# CH32F203RCT6-R1.net
KiCad netlist of a schematic drawn in Altium Designer
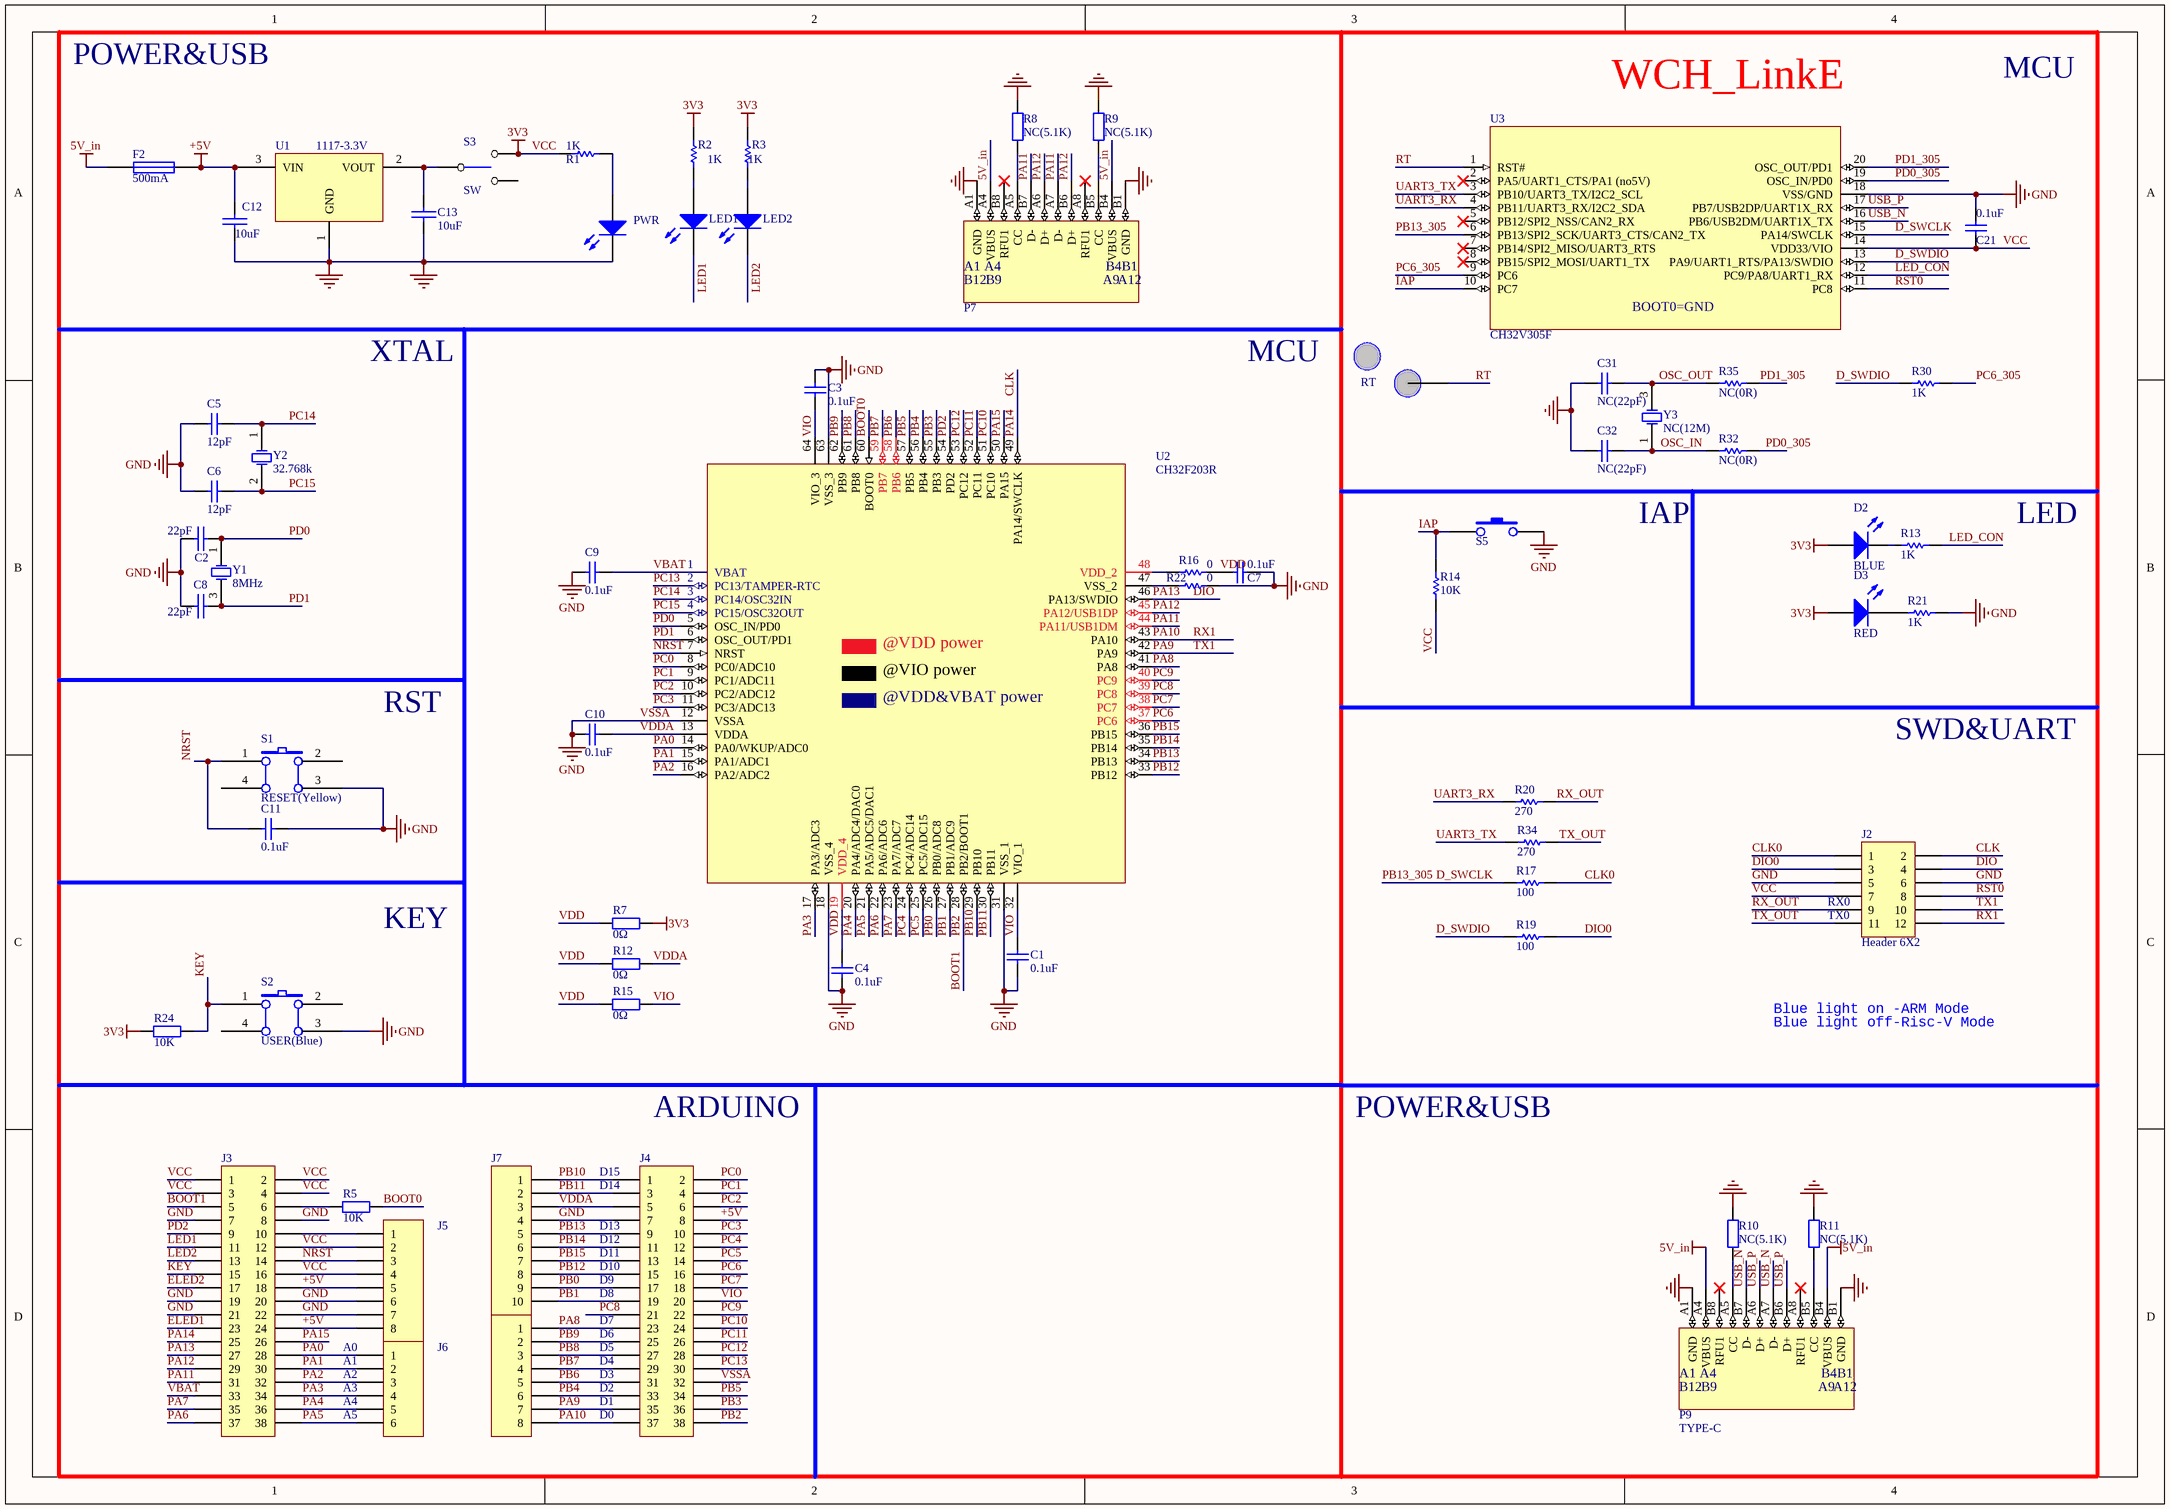
[diagram p0: CH32F203RCT6-R1.SchDoc]

(export (version "E")
  (design (tool "Eeschema 10.0.6"))
  (components
    (comp (ref "C1")
      (value "0.1uF")
      (footprint "0603_C")
      (description "Capacitor")
      (libsource (lib "Miscellaneous Devices") (part "Cap"))
    )
    (comp (ref "C2")
      (value "22pF")
      (footprint "0603_C")
      (description "Capacitor")
      (libsource (lib "*") (part "CAP"))
    )
    (comp (ref "C3")
      (value "0.1uF")
      (footprint "0603_C")
      (description "Capacitor")
      (libsource (lib "Miscellaneous Devices") (part "Cap"))
    )
    (comp (ref "C4")
      (value "0.1uF")
      (footprint "0603_C")
      (description "Capacitor")
      (libsource (lib "Miscellaneous Devices") (part "Cap"))
    )
    (comp (ref "C5")
      (value "12pF")
      (footprint "0603_C")
      (description "Capacitor")
      (libsource (lib "Miscellaneous Devices") (part "Cap"))
    )
    (comp (ref "C6")
      (value "12pF")
      (footprint "0603_C")
      (description "Capacitor")
      (libsource (lib "Miscellaneous Devices") (part "Cap"))
    )
    (comp (ref "C7")
      (value "0.1uF")
      (footprint "0603_C")
      (description "Capacitor")
      (libsource (lib "Miscellaneous Devices") (part "Cap"))
    )
    (comp (ref "C8")
      (value "22pF")
      (footprint "0603_C")
      (description "Capacitor")
      (libsource (lib "*") (part "CAP"))
    )
    (comp (ref "C9")
      (value "0.1uF")
      (footprint "0603_C")
      (description "Capacitor")
      (libsource (lib "Miscellaneous Devices") (part "Cap"))
    )
    (comp (ref "C10")
      (value "0.1uF")
      (footprint "0603_C")
      (description "Capacitor")
      (libsource (lib "Miscellaneous Devices") (part "Cap"))
    )
    (comp (ref "C11")
      (value "0.1uF")
      (footprint "0603_C")
      (description "Capacitor")
      (libsource (lib "Miscellaneous Devices") (part "Cap"))
    )
    (comp (ref "C12")
      (value "10uF")
      (footprint "3216_C")
      (description "Capacitor")
      (libsource (lib "*") (part "CAP"))
    )
    (comp (ref "C13")
      (value "10uF")
      (footprint "3216_C")
      (description "Capacitor")
      (libsource (lib "*") (part "CAP"))
    )
    (comp (ref "C21")
      (value "0.1uF")
      (footprint "0603_C")
      (description "Capacitor")
      (libsource (lib "Miscellaneous Devices") (part "Cap"))
    )
    (comp (ref "C31")
      (value "NC(22pF)")
      (footprint "0603_C")
      (description "Capacitor")
      (fields (field (name "PUBLISHER") "Altium Limited"))
      (libsource (lib "*") (part "Cap"))
    )
    (comp (ref "C32")
      (value "NC(22pF)")
      (footprint "0603_C")
      (description "Capacitor")
      (fields (field (name "PUBLISHER") "Altium Limited"))
      (libsource (lib "*") (part "Cap"))
    )
    (comp (ref "D2")
      (value "BLUE")
      (footprint "0603+")
      (description "Typical RED, GREEN, YELLOW, AMBER GaAs LED")
      (fields (field (name "PUBLISHER") "Altium Limited"))
      (libsource (lib "MYLIB") (part "D0603"))
    )
    (comp (ref "D3")
      (value "RED")
      (footprint "0603+")
      (description "Typical RED, GREEN, YELLOW, AMBER GaAs LED")
      (fields (field (name "PUBLISHER") "Altium Limited"))
      (libsource (lib "MYLIB") (part "D0603"))
    )
    (comp (ref "F2")
      (value "500mA")
      (footprint "0805")
      (description "Fuse")
      (libsource (lib "*") (part "FUSE1"))
    )
    (comp (ref "J2")
      (value "Header 6X2")
      (footprint "IDC12-2.54mm")
      (description "Header, 6-Pin, Dual row")
      (fields (field (name "PUBLISHER") "Altium Limited"))
      (libsource (lib "Miscellaneous Connectors") (part "Header 6X2"))
    )
    (comp (ref "J3")
      (value "Header 19X2")
      (footprint "IDC38-2.54mm")
      (description "Header, 19-Pin, Dual row")
      (fields (field (name "PUBLISHER") "Altium Limited"))
      (libsource (lib "Miscellaneous Connectors") (part "Header 19X2"))
    )
    (comp (ref "J4")
      (value "Header 19X2")
      (footprint "IDC38-2.54mm")
      (description "Header, 19-Pin, Dual row")
      (fields (field (name "PUBLISHER") "Altium Limited"))
      (libsource (lib "Miscellaneous Connectors") (part "Header 19X2"))
    )
    (comp (ref "J5")
      (value "Header 8")
      (footprint "SIP8-2.54mm")
      (description "Header, 8-Pin")
      (fields (field (name "PUBLISHER") "Altium Limited"))
      (libsource (lib "") (part "Header 8_1"))
    )
    (comp (ref "J6")
      (value "Header 6")
      (footprint "SIP6-2.54MM")
      (description "Header, 6-Pin")
      (fields (field (name "PUBLISHER") "Altium Limited"))
      (libsource (lib "Miscellaneous Connectors") (part "Header 6"))
    )
    (comp (ref "J7")
      (value "Header 10")
      (footprint "SIP10-2.54mm")
      (description "Header, 10-Pin")
      (fields (field (name "PUBLISHER") "Altium Limited"))
      (libsource (lib "Miscellaneous Connectors") (part "Header 10"))
    )
    (comp (ref "J8")
      (value "Header 8")
      (footprint "SIP8-2.54mm")
      (description "Header, 8-Pin")
      (fields (field (name "PUBLISHER") "Altium Limited"))
      (libsource (lib "Miscellaneous Connectors") (part "Header 8"))
    )
    (comp (ref "LED1")
      (value "LED1   blue")
      (footprint "0603+")
      (description "Typical INFRARED GaAs LED")
      (fields (field (name "PUBLISHER") "Altium Limited"))
      (libsource (lib "Miscellaneous Devices") (part "LED0"))
    )
    (comp (ref "LED2")
      (value "LED2  blue")
      (footprint "0603+")
      (description "Typical INFRARED GaAs LED")
      (fields (field (name "PUBLISHER") "Altium Limited"))
      (libsource (lib "Miscellaneous Devices") (part "LED0"))
    )
    (comp (ref "P7")
      (value "TYPE-C")
      (footprint "TYPE-C-Receptacle-2.0")
      (libsource (lib "*") (part "TYPE-C1"))
    )
    (comp (ref "P9")
      (value "TYPE-C")
      (footprint "TYPE-C-Receptacle-2.0")
      (libsource (lib "*") (part "TYPE-C1"))
    )
    (comp (ref "PWR")
      (value "POWER  red")
      (footprint "0603+")
      (description "Typical INFRARED GaAs LED")
      (fields (field (name "PUBLISHER") "Altium Limited"))
      (libsource (lib "Miscellaneous Devices") (part "LED0"))
    )
    (comp (ref "R1")
      (value "1K")
      (footprint "0603")
      (description "Semiconductor Resistor")
      (libsource (lib "Miscellaneous Devices") (part "Res Semi"))
    )
    (comp (ref "R2")
      (value "1K")
      (footprint "0603")
      (description "Semiconductor Resistor")
      (libsource (lib "Miscellaneous Devices") (part "Res Semi"))
    )
    (comp (ref "R3")
      (value "1K")
      (footprint "0603")
      (description "Semiconductor Resistor")
      (libsource (lib "Miscellaneous Devices") (part "Res Semi"))
    )
    (comp (ref "R5")
      (value "10K")
      (footprint "0603")
      (description "Resistor")
      (libsource (lib "") (part "Res2_2"))
    )
    (comp (ref "R7")
      (value "0Ω")
      (footprint "0603")
      (description "Resistor")
      (libsource (lib "Miscellaneous Devices") (part "Res2"))
    )
    (comp (ref "R8")
      (value "NC(5.1K)")
      (footprint "0603")
      (description "Resistor")
      (libsource (lib "") (part "Res2_3"))
    )
    (comp (ref "R9")
      (value "NC(5.1K)")
      (footprint "0603")
      (description "Resistor")
      (libsource (lib "") (part "Res2_3"))
    )
    (comp (ref "R10")
      (value "NC(5.1K)")
      (footprint "0603")
      (description "Resistor")
      (libsource (lib "") (part "Res2_1"))
    )
    (comp (ref "R11")
      (value "NC(5.1K)")
      (footprint "0603")
      (description "Resistor")
      (libsource (lib "") (part "Res2_1"))
    )
    (comp (ref "R12")
      (value "0Ω")
      (footprint "0603")
      (description "Resistor")
      (libsource (lib "Miscellaneous Devices") (part "Res2"))
    )
    (comp (ref "R13")
      (value "1K")
      (footprint "0603")
      (description "Resistor")
      (fields (field (name "PUBLISHER") "Altium Limited"))
      (libsource (lib "MYLIB") (part "0603-1"))
    )
    (comp (ref "R14")
      (value "10K")
      (footprint "0603")
      (description "Resistor")
      (fields (field (name "PUBLISHER") "Altium Limited"))
      (libsource (lib "MYLIB") (part "0603-1"))
    )
    (comp (ref "R15")
      (value "0Ω")
      (footprint "0603")
      (description "Resistor")
      (libsource (lib "Miscellaneous Devices") (part "Res2"))
    )
    (comp (ref "R16")
      (value "0")
      (footprint "0603")
      (description "Resistor")
      (fields (field (name "PUBLISHER") "Altium Limited"))
      (libsource (lib "MYLIB") (part "0603-1"))
    )
    (comp (ref "R17")
      (value "100")
      (footprint "0603")
      (description "Resistor")
      (fields (field (name "PUBLISHER") "Altium Limited"))
      (libsource (lib "MYLIB") (part "0603-1"))
    )
    (comp (ref "R19")
      (value "100")
      (footprint "0603")
      (description "Resistor")
      (fields (field (name "PUBLISHER") "Altium Limited"))
      (libsource (lib "MYLIB") (part "0603-1"))
    )
    (comp (ref "R20")
      (value "270")
      (footprint "0603")
      (description "Resistor")
      (fields (field (name "PUBLISHER") "Altium Limited"))
      (libsource (lib "MYLIB") (part "0603-1"))
    )
    (comp (ref "R21")
      (value "1K")
      (footprint "0603")
      (description "Resistor")
      (fields (field (name "PUBLISHER") "Altium Limited"))
      (libsource (lib "MYLIB") (part "0603-1"))
    )
    (comp (ref "R22")
      (value "0")
      (footprint "0603")
      (description "Resistor")
      (fields (field (name "PUBLISHER") "Altium Limited"))
      (libsource (lib "MYLIB") (part "0603-1"))
    )
    (comp (ref "R24")
      (value "10K")
      (footprint "0603")
      (description "Resistor")
      (libsource (lib "Miscellaneous Devices") (part "Res2"))
    )
    (comp (ref "R30")
      (value "1K")
      (footprint "0603")
      (description "Resistor")
      (fields (field (name "PUBLISHER") "Altium Limited"))
      (libsource (lib "MYLIB") (part "0603-1"))
    )
    (comp (ref "R32")
      (value "NC(0R)")
      (footprint "0603")
      (description "Resistor")
      (fields (field (name "PUBLISHER") "Altium Limited"))
      (libsource (lib "MYLIB") (part "0603-1"))
    )
    (comp (ref "R34")
      (value "270")
      (footprint "0603")
      (description "Resistor")
      (fields (field (name "PUBLISHER") "Altium Limited"))
      (libsource (lib "MYLIB") (part "0603-1"))
    )
    (comp (ref "R35")
      (value "NC(0R)")
      (footprint "0603")
      (description "Resistor")
      (fields (field (name "PUBLISHER") "Altium Limited"))
      (libsource (lib "MYLIB") (part "0603-1"))
    )
    (comp (ref "RT")
      (value "Testpoint")
      (footprint "TESTPOINT1")
      (description "测试点")
      (libsource (lib "wch_sch_others") (part "Testpoint"))
    )
    (comp (ref "S1")
      (value "RESET(Yellow)")
      (footprint "KEYX")
      (description "SE PUSHBUTTON")
      (libsource (lib "Documents") (part "SW PUSHBUTTON"))
    )
    (comp (ref "S2")
      (value "USER(Blue)")
      (footprint "KEYX")
      (description "SE PUSHBUTTON")
      (libsource (lib "Documents") (part "SW PUSHBUTTON"))
    )
    (comp (ref "S3") (value "SW") (footprint "SW1") (libsource (lib "MYSCH") (part "SW")))
    (comp (ref "S5") (value "KEY") (footprint "贴片按键") (libsource (lib "*") (part "KEY")))
    (comp (ref "U1")
      (value "1117-3.3V")
      (footprint "SOT-223")
      (libsource (lib "wch_sch_others") (part "1117-3.3V"))
    )
    (comp (ref "U2")
      (value "CH32F203R")
      (footprint "LQFP64M_10x10")
      (description "ARM M3 HD-MCU, 144MHz, 8*UART, 10*Timer, 4*OPA")
      (libsource (lib "CHXXX") (part "CH32F203R"))
    )
    (comp (ref "U3")
      (value "CH32V305F")
      (footprint "TSSOP20")
      (description "RISC-V FPU HD-MCU, 144MHz, USB_480M, CAN, UART*2, SPI")
      (libsource (lib "CHXXX") (part "CH32V305F"))
    )
    (comp (ref "Y1")
      (value "8MHz")
      (footprint "XT3225")
      (description "Crystal Oscillator")
      (fields (field (name "PUBLISHER") "Altium Limited"))
      (libsource (lib "*") (part "XTAL"))
    )
    (comp (ref "Y2")
      (value "32.768k")
      (footprint "FC-135")
      (description "Crystal Oscillator")
      (fields (field (name "PUBLISHER") "Altium Limited"))
      (libsource (lib "Miscellaneous Devices") (part "XTAL"))
    )
    (comp (ref "Y3")
      (value "NC(12M)")
      (footprint "XT3225")
      (description "Crystal Oscillator")
      (libsource (lib "*") (part "XTAL"))
    )
  )
  (nets
    (net (code "1") (name "+5V") (class "Default")
      (node (ref "C12") (pin "1") (pinfunction "1_1") (pintype "passive"))
      (node (ref "F2") (pin "2") (pinfunction "2_2") (pintype "passive"))
      (node (ref "J3") (pin "18") (pinfunction "18_18") (pintype "passive"))
      (node (ref "J3") (pin "24") (pinfunction "24_24") (pintype "passive"))
      (node (ref "J4") (pin "8") (pinfunction "8_8") (pintype "passive"))
      (node (ref "J5") (pin "5") (pinfunction "5_5") (pintype "passive"))
      (node (ref "J5") (pin "8") (pinfunction "8_8") (pintype "passive"))
      (node (ref "U1") (pin "3") (pinfunction "VIN_3") (pintype "passive"))
    )
    (net (code "2") (name "/BOOT0") (class "Default")
      (node (ref "R5") (pin "2") (pinfunction "2_2") (pintype "passive"))
      (node (ref "U2") (pin "60") (pinfunction "BOOT0_60") (pintype "input"))
    )
    (net (code "3") (name "/BOOT1") (class "Default")
      (node (ref "J3") (pin "5") (pinfunction "5_5") (pintype "passive"))
      (node (ref "J4") (pin "38") (pinfunction "38_38") (pintype "passive"))
      (node (ref "U2") (pin "28") (pinfunction "PB2/BOOT1_28") (pintype "bidirectional"))
    )
    (net (code "4") (name "/CLK") (class "Default")
      (node (ref "J2") (pin "2") (pinfunction "2_2") (pintype "passive"))
      (node (ref "J3") (pin "25") (pinfunction "25_25") (pintype "passive"))
      (node (ref "U2") (pin "49") (pinfunction "PA14/SWCLK_49") (pintype "bidirectional"))
    )
    (net (code "5") (name "/CLK0") (class "Default")
      (node (ref "J2") (pin "1") (pinfunction "1_1") (pintype "passive"))
      (node (ref "R17") (pin "1") (pinfunction "1_1") (pintype "passive"))
    )
    (net (code "6") (name "/DIO") (class "Default")
      (node (ref "J2") (pin "4") (pinfunction "4_4") (pintype "passive"))
      (node (ref "J3") (pin "27") (pinfunction "27_27") (pintype "passive"))
      (node (ref "U2") (pin "46") (pinfunction "PA13/SWDIO_46") (pintype "bidirectional"))
    )
    (net (code "7") (name "/DIO0") (class "Default")
      (node (ref "J2") (pin "3") (pinfunction "3_3") (pintype "passive"))
      (node (ref "R19") (pin "1") (pinfunction "1_1") (pintype "passive"))
    )
    (net (code "8") (name "/D_SWCLK") (class "Default")
      (node (ref "R17") (pin "2") (pinfunction "2_2") (pintype "passive"))
      (node (ref "U3") (pin "15") (pinfunction "PA14/SWCLK_15") (pintype "bidirectional"))
      (node (ref "U3") (pin "6") (pinfunction "PB13/SPI2_SCK/UART3_CTS/CAN2_TX_6") (pintype "bidirectional"))
    )
    (net (code "9") (name "/D_SWDIO") (class "Default")
      (node (ref "R19") (pin "2") (pinfunction "2_2") (pintype "passive"))
      (node (ref "R30") (pin "1") (pinfunction "1_1") (pintype "passive"))
      (node (ref "U3") (pin "13") (pinfunction "PA9/UART1_RTS/PA13/SWDIO_13") (pintype "bidirectional"))
    )
    (net (code "10") (name "/ELED1") (class "Default")
      (node (ref "J3") (pin "23") (pinfunction "23_23") (pintype "passive"))
    )
    (net (code "11") (name "/ELED2") (class "Default")
      (node (ref "J3") (pin "17") (pinfunction "17_17") (pintype "passive"))
    )
    (net (code "12") (name "/IAP") (class "Default")
      (node (ref "R14") (pin "1") (pinfunction "1_1") (pintype "passive"))
      (node (ref "S5") (pin "1") (pinfunction "1_1") (pintype "passive"))
      (node (ref "U3") (pin "10") (pinfunction "PC7_10") (pintype "bidirectional"))
    )
    (net (code "13") (name "/KEY") (class "Default")
      (node (ref "J3") (pin "15") (pinfunction "15_15") (pintype "passive"))
      (node (ref "R24") (pin "1") (pinfunction "1_1") (pintype "passive"))
      (node (ref "S2") (pin "1") (pinfunction "A0_1") (pintype "passive"))
    )
    (net (code "14") (name "/LED1") (class "Default")
      (node (ref "J3") (pin "11") (pinfunction "11_11") (pintype "passive"))
      (node (ref "LED1") (pin "2") (pinfunction "K_2") (pintype "passive"))
    )
    (net (code "15") (name "/LED2") (class "Default")
      (node (ref "J3") (pin "13") (pinfunction "13_13") (pintype "passive"))
      (node (ref "LED2") (pin "2") (pinfunction "K_2") (pintype "passive"))
    )
    (net (code "16") (name "/LED_CON") (class "Default")
      (node (ref "R13") (pin "1") (pinfunction "1_1") (pintype "passive"))
      (node (ref "U3") (pin "12") (pinfunction "PC9/PA8/UART1_RX_12") (pintype "bidirectional"))
    )
    (net (code "17") (name "/NRST") (class "Default")
      (node (ref "C11") (pin "2") (pinfunction "2_2") (pintype "passive"))
      (node (ref "J3") (pin "14") (pinfunction "14_14") (pintype "passive"))
      (node (ref "J5") (pin "3") (pinfunction "3_3") (pintype "passive"))
      (node (ref "S1") (pin "1") (pinfunction "A0_1") (pintype "passive"))
      (node (ref "U2") (pin "7") (pinfunction "NRST_7") (pintype "input"))
    )
    (net (code "18") (name "/OSC_IN") (class "Default")
      (node (ref "C32") (pin "2") (pinfunction "2_2") (pintype "passive"))
      (node (ref "R32") (pin "2") (pinfunction "2_2") (pintype "passive"))
      (node (ref "Y3") (pin "1") (pinfunction "OSC1_1") (pintype "passive"))
    )
    (net (code "19") (name "/OSC_OUT") (class "Default")
      (node (ref "C31") (pin "2") (pinfunction "2_2") (pintype "passive"))
      (node (ref "R35") (pin "2") (pinfunction "2_2") (pintype "passive"))
      (node (ref "Y3") (pin "3") (pinfunction "OSC2_3") (pintype "passive"))
    )
    (net (code "20") (name "/PA0") (class "Default")
      (node (ref "J3") (pin "28") (pinfunction "28_28") (pintype "passive"))
      (node (ref "J6") (pin "1") (pinfunction "1_1") (pintype "passive"))
      (node (ref "U2") (pin "14") (pinfunction "PA0/WKUP/ADC0_14") (pintype "bidirectional"))
    )
    (net (code "21") (name "/PA1") (class "Default")
      (node (ref "J3") (pin "30") (pinfunction "30_30") (pintype "passive"))
      (node (ref "J6") (pin "2") (pinfunction "2_2") (pintype "passive"))
      (node (ref "U2") (pin "15") (pinfunction "PA1/ADC1_15") (pintype "bidirectional"))
    )
    (net (code "22") (name "/PA2") (class "Default")
      (node (ref "J3") (pin "32") (pinfunction "32_32") (pintype "passive"))
      (node (ref "J6") (pin "3") (pinfunction "3_3") (pintype "passive"))
      (node (ref "U2") (pin "16") (pinfunction "PA2/ADC2_16") (pintype "bidirectional"))
    )
    (net (code "23") (name "/PA3") (class "Default")
      (node (ref "J3") (pin "34") (pinfunction "34_34") (pintype "passive"))
      (node (ref "J6") (pin "4") (pinfunction "4_4") (pintype "passive"))
      (node (ref "U2") (pin "17") (pinfunction "PA3/ADC3_17") (pintype "bidirectional"))
    )
    (net (code "24") (name "/PA4") (class "Default")
      (node (ref "J3") (pin "36") (pinfunction "36_36") (pintype "passive"))
      (node (ref "J6") (pin "5") (pinfunction "5_5") (pintype "passive"))
      (node (ref "U2") (pin "20") (pinfunction "PA4/ADC4/DAC0_20") (pintype "bidirectional"))
    )
    (net (code "25") (name "/PA5") (class "Default")
      (node (ref "J3") (pin "38") (pinfunction "38_38") (pintype "passive"))
      (node (ref "J6") (pin "6") (pinfunction "6_6") (pintype "passive"))
      (node (ref "U2") (pin "21") (pinfunction "PA5/ADC5/DAC1_21") (pintype "bidirectional"))
    )
    (net (code "26") (name "/PA6") (class "Default")
      (node (ref "J3") (pin "37") (pinfunction "37_37") (pintype "passive"))
      (node (ref "U2") (pin "22") (pinfunction "PA6/ADC6_22") (pintype "bidirectional"))
    )
    (net (code "27") (name "/PA7") (class "Default")
      (node (ref "J3") (pin "35") (pinfunction "35_35") (pintype "passive"))
      (node (ref "U2") (pin "23") (pinfunction "PA7/ADC7_23") (pintype "bidirectional"))
    )
    (net (code "28") (name "/PA8") (class "Default")
      (node (ref "J4") (pin "23") (pinfunction "23_23") (pintype "passive"))
      (node (ref "J8") (pin "1") (pinfunction "1_1") (pintype "passive"))
      (node (ref "U2") (pin "41") (pinfunction "PA8_41") (pintype "bidirectional"))
    )
    (net (code "29") (name "/PA9") (class "Default")
      (node (ref "J2") (pin "10") (pinfunction "10_10") (pintype "passive"))
      (node (ref "J4") (pin "35") (pinfunction "35_35") (pintype "passive"))
      (node (ref "J8") (pin "7") (pinfunction "7_7") (pintype "passive"))
      (node (ref "U2") (pin "42") (pinfunction "PA9_42") (pintype "bidirectional"))
    )
    (net (code "30") (name "/PA10") (class "Default")
      (node (ref "J2") (pin "12") (pinfunction "12_12") (pintype "passive"))
      (node (ref "J4") (pin "37") (pinfunction "37_37") (pintype "passive"))
      (node (ref "J8") (pin "8") (pinfunction "8_8") (pintype "passive"))
      (node (ref "U2") (pin "43") (pinfunction "PA10_43") (pintype "bidirectional"))
    )
    (net (code "31") (name "/PA11") (class "Default")
      (node (ref "J3") (pin "31") (pinfunction "31_31") (pintype "passive"))
      (node (ref "P7") (pin "A7") (pinfunction "D-_A7") (pintype "bidirectional"))
      (node (ref "P7") (pin "B7") (pinfunction "D-_B7") (pintype "bidirectional"))
      (node (ref "U2") (pin "44") (pinfunction "PA11/USB1DM_44") (pintype "bidirectional"))
    )
    (net (code "32") (name "/PA12") (class "Default")
      (node (ref "J3") (pin "29") (pinfunction "29_29") (pintype "passive"))
      (node (ref "P7") (pin "A6") (pinfunction "D+_A6") (pintype "bidirectional"))
      (node (ref "P7") (pin "B6") (pinfunction "D+_B6") (pintype "bidirectional"))
      (node (ref "U2") (pin "45") (pinfunction "PA12/USB1DP_45") (pintype "bidirectional"))
    )
    (net (code "33") (name "/PA15") (class "Default")
      (node (ref "J3") (pin "26") (pinfunction "26_26") (pintype "passive"))
      (node (ref "U2") (pin "50") (pinfunction "PA15_50") (pintype "bidirectional"))
    )
    (net (code "34") (name "/PB0") (class "Default")
      (node (ref "J4") (pin "17") (pinfunction "17_17") (pintype "passive"))
      (node (ref "J7") (pin "9") (pinfunction "9_9") (pintype "passive"))
      (node (ref "U2") (pin "26") (pinfunction "PB0/ADC8_26") (pintype "bidirectional"))
    )
    (net (code "35") (name "/PB1") (class "Default")
      (node (ref "J4") (pin "19") (pinfunction "19_19") (pintype "passive"))
      (node (ref "J7") (pin "10") (pinfunction "10_10") (pintype "passive"))
      (node (ref "U2") (pin "27") (pinfunction "PB1/ADC9_27") (pintype "bidirectional"))
    )
    (net (code "36") (name "/PB3") (class "Default")
      (node (ref "J4") (pin "36") (pinfunction "36_36") (pintype "passive"))
      (node (ref "U2") (pin "55") (pinfunction "PB3_55") (pintype "bidirectional"))
    )
    (net (code "37") (name "/PB4") (class "Default")
      (node (ref "J4") (pin "33") (pinfunction "33_33") (pintype "passive"))
      (node (ref "J8") (pin "6") (pinfunction "6_6") (pintype "passive"))
      (node (ref "U2") (pin "56") (pinfunction "PB4_56") (pintype "bidirectional"))
    )
    (net (code "38") (name "/PB5") (class "Default")
      (node (ref "J4") (pin "34") (pinfunction "34_34") (pintype "passive"))
      (node (ref "U2") (pin "57") (pinfunction "PB5_57") (pintype "bidirectional"))
    )
    (net (code "39") (name "/PB6") (class "Default")
      (node (ref "J4") (pin "31") (pinfunction "31_31") (pintype "passive"))
      (node (ref "J8") (pin "5") (pinfunction "5_5") (pintype "passive"))
      (node (ref "U2") (pin "58") (pinfunction "PB6_58") (pintype "bidirectional"))
    )
    (net (code "40") (name "/PB7") (class "Default")
      (node (ref "J4") (pin "29") (pinfunction "29_29") (pintype "passive"))
      (node (ref "J8") (pin "4") (pinfunction "4_4") (pintype "passive"))
      (node (ref "U2") (pin "59") (pinfunction "PB7_59") (pintype "bidirectional"))
    )
    (net (code "41") (name "/PB8") (class "Default")
      (node (ref "J4") (pin "27") (pinfunction "27_27") (pintype "passive"))
      (node (ref "J8") (pin "3") (pinfunction "3_3") (pintype "passive"))
      (node (ref "U2") (pin "61") (pinfunction "PB8_61") (pintype "bidirectional"))
    )
    (net (code "42") (name "/PB9") (class "Default")
      (node (ref "J4") (pin "25") (pinfunction "25_25") (pintype "passive"))
      (node (ref "J8") (pin "2") (pinfunction "2_2") (pintype "passive"))
      (node (ref "U2") (pin "62") (pinfunction "PB9_62") (pintype "bidirectional"))
    )
    (net (code "43") (name "/PB10") (class "Default")
      (node (ref "J4") (pin "1") (pinfunction "1_1") (pintype "passive"))
      (node (ref "J7") (pin "1") (pinfunction "1_1") (pintype "passive"))
      (node (ref "U2") (pin "29") (pinfunction "PB10_29") (pintype "bidirectional"))
    )
    (net (code "44") (name "/PB11") (class "Default")
      (node (ref "J4") (pin "3") (pinfunction "3_3") (pintype "passive"))
      (node (ref "J7") (pin "2") (pinfunction "2_2") (pintype "passive"))
      (node (ref "U2") (pin "30") (pinfunction "PB11_30") (pintype "bidirectional"))
    )
    (net (code "45") (name "/PB12") (class "Default")
      (node (ref "J4") (pin "15") (pinfunction "15_15") (pintype "passive"))
      (node (ref "J7") (pin "8") (pinfunction "8_8") (pintype "passive"))
      (node (ref "U2") (pin "33") (pinfunction "PB12_33") (pintype "bidirectional"))
    )
    (net (code "46") (name "/PB13") (class "Default")
      (node (ref "J4") (pin "9") (pinfunction "9_9") (pintype "passive"))
      (node (ref "J7") (pin "5") (pinfunction "5_5") (pintype "passive"))
      (node (ref "U2") (pin "34") (pinfunction "PB13_34") (pintype "bidirectional"))
    )
    (net (code "47") (name "/PB14") (class "Default")
      (node (ref "J4") (pin "11") (pinfunction "11_11") (pintype "passive"))
      (node (ref "J7") (pin "6") (pinfunction "6_6") (pintype "passive"))
      (node (ref "U2") (pin "35") (pinfunction "PB14_35") (pintype "bidirectional"))
    )
    (net (code "48") (name "/PB15") (class "Default")
      (node (ref "J4") (pin "13") (pinfunction "13_13") (pintype "passive"))
      (node (ref "J7") (pin "7") (pinfunction "7_7") (pintype "passive"))
      (node (ref "U2") (pin "36") (pinfunction "PB15_36") (pintype "bidirectional"))
    )
    (net (code "49") (name "/PC0") (class "Default")
      (node (ref "J4") (pin "2") (pinfunction "2_2") (pintype "passive"))
      (node (ref "U2") (pin "8") (pinfunction "PC0/ADC10_8") (pintype "bidirectional"))
    )
    (net (code "50") (name "/PC1") (class "Default")
      (node (ref "J4") (pin "4") (pinfunction "4_4") (pintype "passive"))
      (node (ref "U2") (pin "9") (pinfunction "PC1/ADC11_9") (pintype "bidirectional"))
    )
    (net (code "51") (name "/PC2") (class "Default")
      (node (ref "J4") (pin "6") (pinfunction "6_6") (pintype "passive"))
      (node (ref "U2") (pin "10") (pinfunction "PC2/ADC12_10") (pintype "bidirectional"))
    )
    (net (code "52") (name "/PC3") (class "Default")
      (node (ref "J4") (pin "10") (pinfunction "10_10") (pintype "passive"))
      (node (ref "U2") (pin "11") (pinfunction "PC3/ADC13_11") (pintype "bidirectional"))
    )
    (net (code "53") (name "/PC4") (class "Default")
      (node (ref "J4") (pin "12") (pinfunction "12_12") (pintype "passive"))
      (node (ref "U2") (pin "24") (pinfunction "PC4/ADC14_24") (pintype "bidirectional"))
    )
    (net (code "54") (name "/PC5") (class "Default")
      (node (ref "J4") (pin "14") (pinfunction "14_14") (pintype "passive"))
      (node (ref "U2") (pin "25") (pinfunction "PC5/ADC15_25") (pintype "bidirectional"))
    )
    (net (code "55") (name "/PC6") (class "Default")
      (node (ref "J4") (pin "16") (pinfunction "16_16") (pintype "passive"))
      (node (ref "U2") (pin "37") (pinfunction "PC6_37") (pintype "bidirectional"))
    )
    (net (code "56") (name "/PC6_305") (class "Default")
      (node (ref "R30") (pin "2") (pinfunction "2_2") (pintype "passive"))
      (node (ref "U3") (pin "9") (pinfunction "PC6_9") (pintype "bidirectional"))
    )
    (net (code "57") (name "/PC7") (class "Default")
      (node (ref "J4") (pin "18") (pinfunction "18_18") (pintype "passive"))
      (node (ref "U2") (pin "38") (pinfunction "PC7_38") (pintype "bidirectional"))
    )
    (net (code "58") (name "/PC8") (class "Default")
      (node (ref "J4") (pin "21") (pinfunction "21_21") (pintype "passive"))
      (node (ref "U2") (pin "39") (pinfunction "PC8_39") (pintype "bidirectional"))
    )
    (net (code "59") (name "/PC9") (class "Default")
      (node (ref "J4") (pin "22") (pinfunction "22_22") (pintype "passive"))
      (node (ref "U2") (pin "40") (pinfunction "PC9_40") (pintype "bidirectional"))
    )
    (net (code "60") (name "/PC10") (class "Default")
      (node (ref "J4") (pin "24") (pinfunction "24_24") (pintype "passive"))
      (node (ref "U2") (pin "51") (pinfunction "PC10_51") (pintype "bidirectional"))
    )
    (net (code "61") (name "/PC11") (class "Default")
      (node (ref "J4") (pin "26") (pinfunction "26_26") (pintype "passive"))
      (node (ref "U2") (pin "52") (pinfunction "PC11_52") (pintype "bidirectional"))
    )
    (net (code "62") (name "/PC12") (class "Default")
      (node (ref "J4") (pin "28") (pinfunction "28_28") (pintype "passive"))
      (node (ref "U2") (pin "53") (pinfunction "PC12_53") (pintype "bidirectional"))
    )
    (net (code "63") (name "/PC13") (class "Default")
      (node (ref "J4") (pin "30") (pinfunction "30_30") (pintype "passive"))
      (node (ref "U2") (pin "2") (pinfunction "PC13/TAMPER-RTC_2") (pintype "bidirectional"))
    )
    (net (code "64") (name "/PC14") (class "Default")
      (node (ref "C5") (pin "1") (pinfunction "1_1") (pintype "passive"))
      (node (ref "U2") (pin "3") (pinfunction "PC14/OSC32IN_3") (pintype "bidirectional"))
      (node (ref "Y2") (pin "1") (pinfunction "OSC1_1") (pintype "passive"))
    )
    (net (code "65") (name "/PC15") (class "Default")
      (node (ref "C6") (pin "1") (pinfunction "1_1") (pintype "passive"))
      (node (ref "U2") (pin "4") (pinfunction "PC15/OSC32OUT_4") (pintype "bidirectional"))
      (node (ref "Y2") (pin "2") (pinfunction "OSC2_2") (pintype "passive"))
    )
    (net (code "66") (name "/PD0") (class "Default")
      (node (ref "C2") (pin "2") (pinfunction "2_2") (pintype "passive"))
      (node (ref "U2") (pin "5") (pinfunction "OSC_IN/PD0_5") (pintype "bidirectional"))
      (node (ref "Y1") (pin "1") (pinfunction "OSC1_1") (pintype "passive"))
    )
    (net (code "67") (name "/PD0_305") (class "Default")
      (node (ref "R32") (pin "1") (pinfunction "1_1") (pintype "passive"))
      (node (ref "U3") (pin "19") (pinfunction "OSC_IN/PD0_19") (pintype "bidirectional"))
    )
    (net (code "68") (name "/PD1") (class "Default")
      (node (ref "C8") (pin "2") (pinfunction "2_2") (pintype "passive"))
      (node (ref "U2") (pin "6") (pinfunction "OSC_OUT/PD1_6") (pintype "bidirectional"))
      (node (ref "Y1") (pin "3") (pinfunction "OSC2_3") (pintype "passive"))
    )
    (net (code "69") (name "/PD1_305") (class "Default")
      (node (ref "R35") (pin "1") (pinfunction "1_1") (pintype "passive"))
      (node (ref "U3") (pin "20") (pinfunction "OSC_OUT/PD1_20") (pintype "bidirectional"))
    )
    (net (code "70") (name "/PD2") (class "Default")
      (node (ref "J3") (pin "9") (pinfunction "9_9") (pintype "passive"))
      (node (ref "U2") (pin "54") (pinfunction "PD2_54") (pintype "bidirectional"))
    )
    (net (code "71") (name "/RST0") (class "Default")
      (node (ref "J2") (pin "8") (pinfunction "8_8") (pintype "passive"))
      (node (ref "U3") (pin "11") (pinfunction "PC8_11") (pintype "bidirectional"))
    )
    (net (code "72") (name "/RT") (class "Default")
      (node (ref "RT") (pin "1") (pinfunction "point_1") (pintype "passive"))
      (node (ref "U3") (pin "1") (pinfunction "RST#_1") (pintype "input"))
    )
    (net (code "73") (name "/RX_OUT") (class "Default")
      (node (ref "J2") (pin "9") (pinfunction "9_9") (pintype "passive"))
      (node (ref "R20") (pin "1") (pinfunction "1_1") (pintype "passive"))
    )
    (net (code "74") (name "/TX_OUT") (class "Default")
      (node (ref "J2") (pin "11") (pinfunction "11_11") (pintype "passive"))
      (node (ref "R34") (pin "1") (pinfunction "1_1") (pintype "passive"))
    )
    (net (code "75") (name "/UART3_RX") (class "Default")
      (node (ref "R20") (pin "2") (pinfunction "2_2") (pintype "passive"))
      (node (ref "U3") (pin "4") (pinfunction "PB11/UART3_RX/I2C2_SDA_4") (pintype "bidirectional"))
    )
    (net (code "76") (name "/UART3_TX") (class "Default")
      (node (ref "R34") (pin "2") (pinfunction "2_2") (pintype "passive"))
      (node (ref "U3") (pin "3") (pinfunction "PB10/UART3_TX/I2C2_SCL_3") (pintype "bidirectional"))
    )
    (net (code "77") (name "/USB_N") (class "Default")
      (node (ref "P9") (pin "A7") (pinfunction "D-_A7") (pintype "bidirectional"))
      (node (ref "P9") (pin "B7") (pinfunction "D-_B7") (pintype "bidirectional"))
      (node (ref "U3") (pin "16") (pinfunction "PB6/USB2DM/UART1X_TX_16") (pintype "bidirectional"))
    )
    (net (code "78") (name "/USB_P") (class "Default")
      (node (ref "P9") (pin "A6") (pinfunction "D+_A6") (pintype "bidirectional"))
      (node (ref "P9") (pin "B6") (pinfunction "D+_B6") (pintype "bidirectional"))
      (node (ref "U3") (pin "17") (pinfunction "PB7/USB2DP/UART1X_RX_17") (pintype "bidirectional"))
    )
    (net (code "79") (name "/VBAT") (class "Default")
      (node (ref "C9") (pin "1") (pinfunction "1_1") (pintype "passive"))
      (node (ref "J3") (pin "33") (pinfunction "33_33") (pintype "passive"))
      (node (ref "U2") (pin "1") (pinfunction "VBAT_1") (pintype "power_in"))
    )
    (net (code "80") (name "/VDD") (class "Default")
      (node (ref "C4") (pin "2") (pinfunction "2_2") (pintype "passive"))
      (node (ref "C7") (pin "2") (pinfunction "2_2") (pintype "passive"))
      (node (ref "R12") (pin "2") (pinfunction "2_2") (pintype "passive"))
      (node (ref "R15") (pin "2") (pinfunction "2_2") (pintype "passive"))
      (node (ref "R16") (pin "1") (pinfunction "1_1") (pintype "passive"))
      (node (ref "R7") (pin "2") (pinfunction "2_2") (pintype "passive"))
      (node (ref "U2") (pin "19") (pinfunction "VDD_4_19") (pintype "power_in"))
    )
    (net (code "81") (name "/VDDA") (class "Default")
      (node (ref "C10") (pin "1") (pinfunction "1_1") (pintype "passive"))
      (node (ref "J4") (pin "5") (pinfunction "5_5") (pintype "passive"))
      (node (ref "J7") (pin "3") (pinfunction "3_3") (pintype "passive"))
      (node (ref "R12") (pin "1") (pinfunction "1_1") (pintype "passive"))
      (node (ref "U2") (pin "13") (pinfunction "VDDA_13") (pintype "power_in"))
    )
    (net (code "82") (name "/VIO") (class "Default")
      (node (ref "C1") (pin "2") (pinfunction "2_2") (pintype "passive"))
      (node (ref "C3") (pin "2") (pinfunction "2_2") (pintype "passive"))
      (node (ref "J4") (pin "20") (pinfunction "20_20") (pintype "passive"))
      (node (ref "R15") (pin "1") (pinfunction "1_1") (pintype "passive"))
      (node (ref "U2") (pin "32") (pinfunction "VIO_1_32") (pintype "power_in"))
      (node (ref "U2") (pin "64") (pinfunction "VIO_3_64") (pintype "power_in"))
    )
    (net (code "83") (name "3V3") (class "Default")
      (node (ref "C21") (pin "1") (pinfunction "1_1") (pintype "passive"))
      (node (ref "D2") (pin "1") (pinfunction "A_1") (pintype "passive"))
      (node (ref "D3") (pin "1") (pinfunction "A_1") (pintype "passive"))
      (node (ref "J2") (pin "7") (pinfunction "7_7") (pintype "passive"))
      (node (ref "J3") (pin "1") (pinfunction "1_1") (pintype "passive"))
      (node (ref "J3") (pin "12") (pinfunction "12_12") (pintype "passive"))
      (node (ref "J3") (pin "16") (pinfunction "16_16") (pintype "passive"))
      (node (ref "J3") (pin "2") (pinfunction "2_2") (pintype "passive"))
      (node (ref "J3") (pin "3") (pinfunction "3_3") (pintype "passive"))
      (node (ref "J3") (pin "4") (pinfunction "4_4") (pintype "passive"))
      (node (ref "J5") (pin "2") (pinfunction "2_2") (pintype "passive"))
      (node (ref "J5") (pin "4") (pinfunction "4_4") (pintype "passive"))
      (node (ref "R1") (pin "2") (pinfunction "2_2") (pintype "passive"))
      (node (ref "R14") (pin "2") (pinfunction "2_2") (pintype "passive"))
      (node (ref "R2") (pin "1") (pinfunction "1_1") (pintype "passive"))
      (node (ref "R24") (pin "2") (pinfunction "2_2") (pintype "passive"))
      (node (ref "R3") (pin "1") (pinfunction "1_1") (pintype "passive"))
      (node (ref "R7") (pin "1") (pinfunction "1_1") (pintype "passive"))
      (node (ref "S3") (pin "3") (pinfunction "3_3") (pintype "passive"))
      (node (ref "U3") (pin "14") (pinfunction "VDD33/VIO_14") (pintype "power_in"))
    )
    (net (code "84") (name "5V_in") (class "Default")
      (node (ref "F2") (pin "1") (pinfunction "1_1") (pintype "passive"))
      (node (ref "P7") (pin "A4") (pinfunction "VBUS_A4") (pintype "bidirectional"))
      (node (ref "P7") (pin "B4") (pinfunction "VBUS_B4") (pintype "bidirectional"))
      (node (ref "P9") (pin "A4") (pinfunction "VBUS_A4") (pintype "bidirectional"))
      (node (ref "P9") (pin "B4") (pinfunction "VBUS_B4") (pintype "bidirectional"))
    )
    (net (code "85") (name "GND") (class "Default")
      (node (ref "C1") (pin "1") (pinfunction "1_1") (pintype "passive"))
      (node (ref "C10") (pin "2") (pinfunction "2_2") (pintype "passive"))
      (node (ref "C11") (pin "1") (pinfunction "1_1") (pintype "passive"))
      (node (ref "C12") (pin "2") (pinfunction "2_2") (pintype "passive"))
      (node (ref "C13") (pin "2") (pinfunction "2_2") (pintype "passive"))
      (node (ref "C2") (pin "1") (pinfunction "1_1") (pintype "passive"))
      (node (ref "C21") (pin "2") (pinfunction "2_2") (pintype "passive"))
      (node (ref "C3") (pin "1") (pinfunction "1_1") (pintype "passive"))
      (node (ref "C31") (pin "1") (pinfunction "1_1") (pintype "passive"))
      (node (ref "C32") (pin "1") (pinfunction "1_1") (pintype "passive"))
      (node (ref "C4") (pin "1") (pinfunction "1_1") (pintype "passive"))
      (node (ref "C5") (pin "2") (pinfunction "2_2") (pintype "passive"))
      (node (ref "C6") (pin "2") (pinfunction "2_2") (pintype "passive"))
      (node (ref "C7") (pin "1") (pinfunction "1_1") (pintype "passive"))
      (node (ref "C8") (pin "1") (pinfunction "1_1") (pintype "passive"))
      (node (ref "C9") (pin "2") (pinfunction "2_2") (pintype "passive"))
      (node (ref "J2") (pin "5") (pinfunction "5_5") (pintype "passive"))
      (node (ref "J2") (pin "6") (pinfunction "6_6") (pintype "passive"))
      (node (ref "J3") (pin "19") (pinfunction "19_19") (pintype "passive"))
      (node (ref "J3") (pin "20") (pinfunction "20_20") (pintype "passive"))
      (node (ref "J3") (pin "21") (pinfunction "21_21") (pintype "passive"))
      (node (ref "J3") (pin "22") (pinfunction "22_22") (pintype "passive"))
      (node (ref "J3") (pin "7") (pinfunction "7_7") (pintype "passive"))
      (node (ref "J3") (pin "8") (pinfunction "8_8") (pintype "passive"))
      (node (ref "J4") (pin "32") (pinfunction "32_32") (pintype "passive"))
      (node (ref "J4") (pin "7") (pinfunction "7_7") (pintype "passive"))
      (node (ref "J5") (pin "6") (pinfunction "6_6") (pintype "passive"))
      (node (ref "J5") (pin "7") (pinfunction "7_7") (pintype "passive"))
      (node (ref "J7") (pin "4") (pinfunction "4_4") (pintype "passive"))
      (node (ref "P7") (pin "A1") (pinfunction "GND_A1") (pintype "bidirectional"))
      (node (ref "P7") (pin "B1") (pinfunction "GND_B1") (pintype "bidirectional"))
      (node (ref "P9") (pin "A1") (pinfunction "GND_A1") (pintype "bidirectional"))
      (node (ref "P9") (pin "B1") (pinfunction "GND_B1") (pintype "bidirectional"))
      (node (ref "PWR") (pin "2") (pinfunction "K_2") (pintype "passive"))
      (node (ref "R10") (pin "2") (pinfunction "2_2") (pintype "passive"))
      (node (ref "R11") (pin "2") (pinfunction "2_2") (pintype "passive"))
      (node (ref "R21") (pin "1") (pinfunction "1_1") (pintype "passive"))
      (node (ref "R22") (pin "1") (pinfunction "1_1") (pintype "passive"))
      (node (ref "R8") (pin "1") (pinfunction "1_1") (pintype "passive"))
      (node (ref "R9") (pin "1") (pinfunction "1_1") (pintype "passive"))
      (node (ref "S1") (pin "3") (pinfunction "B1_3") (pintype "passive"))
      (node (ref "S2") (pin "3") (pinfunction "B1_3") (pintype "passive"))
      (node (ref "S5") (pin "2") (pinfunction "2_2") (pintype "passive"))
      (node (ref "U1") (pin "1") (pinfunction "GND_1") (pintype "passive"))
      (node (ref "U2") (pin "12") (pinfunction "VSSA_12") (pintype "power_in"))
      (node (ref "U2") (pin "18") (pinfunction "VSS_4_18") (pintype "power_in"))
      (node (ref "U2") (pin "31") (pinfunction "VSS_1_31") (pintype "power_in"))
      (node (ref "U2") (pin "63") (pinfunction "VSS_3_63") (pintype "power_in"))
      (node (ref "U3") (pin "18") (pinfunction "VSS/GND_18") (pintype "power_in"))
    )
    (net (code "86") (name "Net-(D2-K)") (class "Default")
      (node (ref "D2") (pin "2") (pinfunction "K_2") (pintype "passive"))
      (node (ref "R13") (pin "2") (pinfunction "2_2") (pintype "passive"))
    )
    (net (code "87") (name "Net-(D3-K)") (class "Default")
      (node (ref "D3") (pin "2") (pinfunction "K_2") (pintype "passive"))
      (node (ref "R21") (pin "2") (pinfunction "2_2") (pintype "passive"))
    )
    (net (code "88") (name "Net-(J3-Pad6)") (class "Default")
      (node (ref "J3") (pin "6") (pinfunction "6_6") (pintype "passive"))
      (node (ref "R5") (pin "1") (pinfunction "1_1") (pintype "passive"))
    )
    (net (code "89") (name "Net-(J3-Pad10)") (class "Default")
      (node (ref "J3") (pin "10") (pinfunction "10_10") (pintype "passive"))
      (node (ref "J5") (pin "1") (pinfunction "1_1") (pintype "passive"))
    )
    (net (code "90") (name "Net-(LED1-A)") (class "Default")
      (node (ref "LED1") (pin "1") (pinfunction "A_1") (pintype "passive"))
      (node (ref "R2") (pin "2") (pinfunction "2_2") (pintype "passive"))
    )
    (net (code "91") (name "Net-(LED2-A)") (class "Default")
      (node (ref "LED2") (pin "1") (pinfunction "A_1") (pintype "passive"))
      (node (ref "R3") (pin "2") (pinfunction "2_2") (pintype "passive"))
    )
    (net (code "92") (name "Net-(P7-CC-PadA5)") (class "Default")
      (node (ref "P7") (pin "A5") (pinfunction "CC_A5") (pintype "bidirectional"))
      (node (ref "R8") (pin "2") (pinfunction "2_2") (pintype "passive"))
    )
    (net (code "93") (name "Net-(P7-CC-PadB5)") (class "Default")
      (node (ref "P7") (pin "B5") (pinfunction "CC_B5") (pintype "bidirectional"))
      (node (ref "R9") (pin "2") (pinfunction "2_2") (pintype "passive"))
    )
    (net (code "94") (name "Net-(P9-CC-PadA5)") (class "Default")
      (node (ref "P9") (pin "A5") (pinfunction "CC_A5") (pintype "bidirectional"))
      (node (ref "R10") (pin "1") (pinfunction "1_1") (pintype "passive"))
    )
    (net (code "95") (name "Net-(P9-CC-PadB5)") (class "Default")
      (node (ref "P9") (pin "B5") (pinfunction "CC_B5") (pintype "bidirectional"))
      (node (ref "R11") (pin "1") (pinfunction "1_1") (pintype "passive"))
    )
    (net (code "96") (name "Net-(PWR-A)") (class "Default")
      (node (ref "PWR") (pin "1") (pinfunction "A_1") (pintype "passive"))
      (node (ref "R1") (pin "1") (pinfunction "1_1") (pintype "passive"))
    )
    (net (code "97") (name "Net-(U1-VOUT)") (class "Default")
      (node (ref "C13") (pin "1") (pinfunction "1_1") (pintype "passive"))
      (node (ref "S3") (pin "1") (pinfunction "1_1") (pintype "passive"))
      (node (ref "U1") (pin "2") (pinfunction "VOUT_2") (pintype "passive"))
    )
    (net (code "98") (name "Net-(U2-VDD_2)") (class "Default")
      (node (ref "R16") (pin "2") (pinfunction "2_2") (pintype "passive"))
      (node (ref "U2") (pin "48") (pinfunction "VDD_2_48") (pintype "power_in"))
    )
    (net (code "99") (name "Net-(U2-VSS_2)") (class "Default")
      (node (ref "R22") (pin "2") (pinfunction "2_2") (pintype "passive"))
      (node (ref "U2") (pin "47") (pinfunction "VSS_2_47") (pintype "power_in"))
    )
    (net (code "100") (name "unconnected-(P7-RFU1-PadA8)") (class "Default")
      (node (ref "P7") (pin "A8") (pinfunction "RFU1_A8") (pintype "bidirectional+no_connect"))
    )
    (net (code "101") (name "unconnected-(P7-RFU1-PadB8)") (class "Default")
      (node (ref "P7") (pin "B8") (pinfunction "RFU1_B8") (pintype "bidirectional+no_connect"))
    )
    (net (code "102") (name "unconnected-(P9-RFU1-PadA8)") (class "Default")
      (node (ref "P9") (pin "A8") (pinfunction "RFU1_A8") (pintype "bidirectional+no_connect"))
    )
    (net (code "103") (name "unconnected-(P9-RFU1-PadB8)") (class "Default")
      (node (ref "P9") (pin "B8") (pinfunction "RFU1_B8") (pintype "bidirectional+no_connect"))
    )
    (net (code "104") (name "unconnected-(S1-A1-Pad4)") (class "Default")
      (node (ref "S1") (pin "4") (pinfunction "A1_4") (pintype "passive"))
    )
    (net (code "105") (name "unconnected-(S1-B0-Pad2)") (class "Default")
      (node (ref "S1") (pin "2") (pinfunction "B0_2") (pintype "passive"))
    )
    (net (code "106") (name "unconnected-(S2-A1-Pad4)") (class "Default")
      (node (ref "S2") (pin "4") (pinfunction "A1_4") (pintype "passive"))
    )
    (net (code "107") (name "unconnected-(S2-B0-Pad2)") (class "Default")
      (node (ref "S2") (pin "2") (pinfunction "B0_2") (pintype "passive"))
    )
    (net (code "108") (name "unconnected-(S3-Pad2)") (class "Default")
      (node (ref "S3") (pin "2") (pinfunction "2_2") (pintype "passive"))
    )
    (net (code "109") (name "unconnected-(U3-PA5{slash}UART1_CTS{slash}PA1_(no5V)-Pad2)") (class "Default")
      (node (ref "U3") (pin "2") (pinfunction "PA5/UART1_CTS/PA1_(no5V)_2") (pintype "bidirectional+no_connect"))
    )
    (net (code "110") (name "unconnected-(U3-PB12{slash}SPI2_NSS{slash}CAN2_RX-Pad5)") (class "Default")
      (node (ref "U3") (pin "5") (pinfunction "PB12/SPI2_NSS/CAN2_RX_5") (pintype "bidirectional+no_connect"))
    )
    (net (code "111") (name "unconnected-(U3-PB14{slash}SPI2_MISO{slash}UART3_RTS-Pad7)") (class "Default")
      (node (ref "U3") (pin "7") (pinfunction "PB14/SPI2_MISO/UART3_RTS_7") (pintype "bidirectional+no_connect"))
    )
    (net (code "112") (name "unconnected-(U3-PB15{slash}SPI2_MOSI{slash}UART1_TX-Pad8)") (class "Default")
      (node (ref "U3") (pin "8") (pinfunction "PB15/SPI2_MOSI/UART1_TX_8") (pintype "bidirectional+no_connect"))
    )
  )
)
